# Gravador.net
KiCad netlist of a schematic drawn in EAGLE
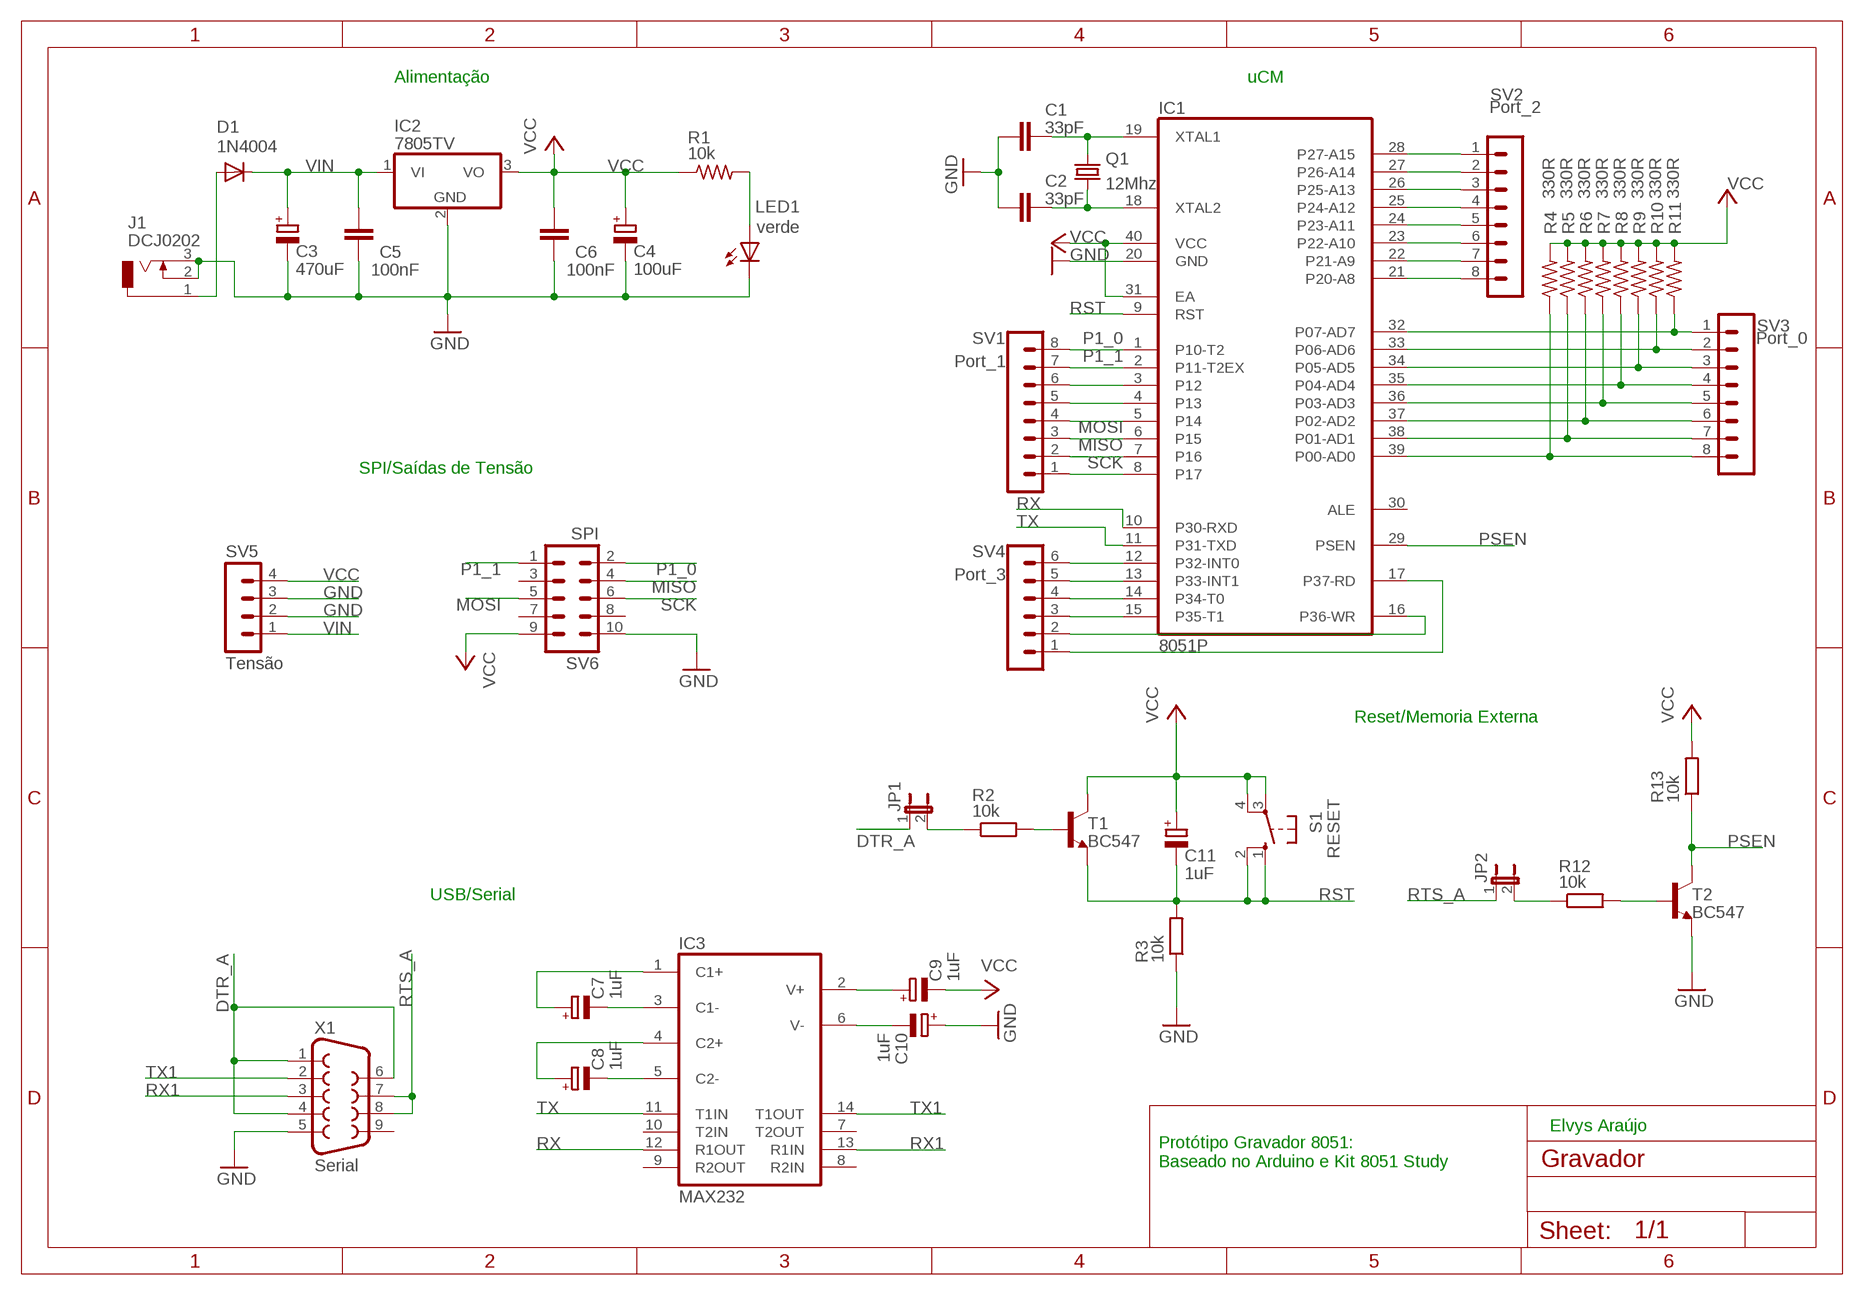
[diagram p0: schematic, sheet 1]

(export (version "E")
  (design (tool "Eeschema 10.0.6"))
  (components
    (comp (ref "C1")
      (value "33pF")
      (footprint "eagle-import:C5B3")
      (libsource (lib "eagle-import") (part "C5/3"))
    )
    (comp (ref "C2")
      (value "33pF")
      (footprint "eagle-import:C5B3")
      (libsource (lib "eagle-import") (part "C5/3"))
    )
    (comp (ref "C3")
      (value "470uF")
      (footprint "eagle-import:E3,5-8")
      (libsource (lib "eagle-import") (part "CPOL-EUE3.5-8"))
    )
    (comp (ref "C4")
      (value "100uF")
      (footprint "eagle-import:E2,5-6E")
      (libsource (lib "eagle-import") (part "CPOL-EUE2,5-6E"))
    )
    (comp (ref "C5")
      (value "100nF")
      (footprint "eagle-import:C5B3")
      (libsource (lib "eagle-import") (part "C5/3"))
    )
    (comp (ref "C6")
      (value "100nF")
      (footprint "eagle-import:C5B3")
      (libsource (lib "eagle-import") (part "C5/3"))
    )
    (comp (ref "C7")
      (value "1uF")
      (footprint "eagle-import:E2,5-6E")
      (libsource (lib "eagle-import") (part "CPOL-EUE2,5-6E"))
    )
    (comp (ref "C8")
      (value "1uF")
      (footprint "eagle-import:E2,5-6E")
      (libsource (lib "eagle-import") (part "CPOL-EUE2,5-6E"))
    )
    (comp (ref "C9")
      (value "1uF")
      (footprint "eagle-import:E2,5-6E")
      (libsource (lib "eagle-import") (part "CPOL-EUE2,5-6E"))
    )
    (comp (ref "C10")
      (value "1uF")
      (footprint "eagle-import:E2,5-6E")
      (libsource (lib "eagle-import") (part "CPOL-EUE2,5-6E"))
    )
    (comp (ref "C11")
      (value "1uF")
      (footprint "eagle-import:E2,5-6E")
      (libsource (lib "eagle-import") (part "CPOL-EUE2,5-6E"))
    )
    (comp (ref "D1")
      (value "1N4004")
      (footprint "eagle-import:DO41-10")
      (libsource (lib "eagle-import") (part "1N4004"))
    )
    (comp (ref "IC1")
      (value "8051P")
      (footprint "eagle-import:DIL40")
      (libsource (lib "eagle-import") (part "8051P"))
    )
    (comp (ref "IC2")
      (value "7805TV")
      (footprint "eagle-import:TO220V")
      (libsource (lib "eagle-import") (part "78TV05"))
    )
    (comp (ref "IC3")
      (value "MAX232")
      (footprint "eagle-import:DIL16")
      (fields (field (name "MF") "MAXIM") (field (name "MPN") "MAX232ACPE+"))
      (libsource (lib "eagle-import") (part "MAX232"))
    )
    (comp (ref "J1")
      (value "DCJ0202")
      (footprint "eagle-import:DCJ0202")
      (libsource (lib "eagle-import") (part "DCJ0202"))
    )
    (comp (ref "JP1")
      (value "JP1E")
      (footprint "eagle-import:JP1")
      (libsource (lib "eagle-import") (part "JP1E"))
    )
    (comp (ref "JP2")
      (value "JP1E")
      (footprint "eagle-import:JP1")
      (libsource (lib "eagle-import") (part "JP1E"))
    )
    (comp (ref "LED1")
      (value "verde")
      (footprint "eagle-import:LED5MM")
      (libsource (lib "eagle-import") (part "LED5MM"))
    )
    (comp (ref "Q1")
      (value "12Mhz")
      (footprint "eagle-import:HC49U-V")
      (libsource (lib "eagle-import") (part "CRYSTALHC49U-V"))
    )
    (comp (ref "R1")
      (value "10k")
      (footprint "eagle-import:0207_2V")
      (libsource (lib "eagle-import") (part "R-US_0207/2V"))
    )
    (comp (ref "R2")
      (value "10k")
      (footprint "eagle-import:0207_10@1")
      (libsource (lib "eagle-import") (part "R-EU_0207/10"))
    )
    (comp (ref "R3")
      (value "10k")
      (footprint "eagle-import:0207_10@1")
      (libsource (lib "eagle-import") (part "R-EU_0207/10"))
    )
    (comp (ref "R4")
      (value "330R")
      (footprint "eagle-import:0207_2V")
      (libsource (lib "eagle-import") (part "R-US_0207/2V"))
    )
    (comp (ref "R5")
      (value "330R")
      (footprint "eagle-import:0207_2V")
      (libsource (lib "eagle-import") (part "R-US_0207/2V"))
    )
    (comp (ref "R6")
      (value "330R")
      (footprint "eagle-import:0207_2V")
      (libsource (lib "eagle-import") (part "R-US_0207/2V"))
    )
    (comp (ref "R7")
      (value "330R")
      (footprint "eagle-import:0207_2V")
      (libsource (lib "eagle-import") (part "R-US_0207/2V"))
    )
    (comp (ref "R8")
      (value "330R")
      (footprint "eagle-import:0207_2V")
      (libsource (lib "eagle-import") (part "R-US_0207/2V"))
    )
    (comp (ref "R9")
      (value "330R")
      (footprint "eagle-import:0207_2V")
      (libsource (lib "eagle-import") (part "R-US_0207/2V"))
    )
    (comp (ref "R10")
      (value "330R")
      (footprint "eagle-import:0207_2V")
      (libsource (lib "eagle-import") (part "R-US_0207/2V"))
    )
    (comp (ref "R11")
      (value "330R")
      (footprint "eagle-import:0207_2V")
      (libsource (lib "eagle-import") (part "R-US_0207/2V"))
    )
    (comp (ref "R12")
      (value "10k")
      (footprint "eagle-import:0207_10@1")
      (libsource (lib "eagle-import") (part "R-EU_0207/10"))
    )
    (comp (ref "R13")
      (value "10k")
      (footprint "eagle-import:0207_10@1")
      (libsource (lib "eagle-import") (part "R-EU_0207/10"))
    )
    (comp (ref "S1")
      (value "RESET")
      (footprint "eagle-import:B3F-10XX")
      (fields (field (name "MPN") "B3F-1000"))
      (libsource (lib "eagle-import") (part "10-XX"))
    )
    (comp (ref "SV1")
      (value "Port_1")
      (footprint "eagle-import:MA08-1")
      (libsource (lib "eagle-import") (part "MA08-1"))
    )
    (comp (ref "SV2")
      (value "Port_2")
      (footprint "eagle-import:MA08-1")
      (libsource (lib "eagle-import") (part "MA08-1"))
    )
    (comp (ref "SV3")
      (value "Port_0")
      (footprint "eagle-import:MA08-1")
      (libsource (lib "eagle-import") (part "MA08-1"))
    )
    (comp (ref "SV4")
      (value "Port_3")
      (footprint "eagle-import:MA06-1")
      (libsource (lib "eagle-import") (part "MA06-1"))
    )
    (comp (ref "SV5")
      (value "Tensão")
      (footprint "eagle-import:MA04-1")
      (libsource (lib "eagle-import") (part "MA04-1"))
    )
    (comp (ref "SV6")
      (value "SPI")
      (footprint "eagle-import:MA05-2")
      (libsource (lib "eagle-import") (part "MA05-2"))
    )
    (comp (ref "T1")
      (value "BC547")
      (footprint "eagle-import:TO92")
      (libsource (lib "eagle-import") (part "BC547"))
    )
    (comp (ref "T2")
      (value "BC547")
      (footprint "eagle-import:TO92")
      (libsource (lib "eagle-import") (part "BC547"))
    )
    (comp (ref "X1")
      (value "Serial")
      (footprint "eagle-import:F09HP")
      (libsource (lib "eagle-import") (part "F09HP"))
    )
  )
  (nets
    (net (code "1") (name "/DTR_A") (class "Default")
      (node (ref "JP1") (pin "1") (pinfunction "1_1") (pintype "passive"))
      (node (ref "X1") (pin "1") (pinfunction "1_1") (pintype "passive"))
      (node (ref "X1") (pin "4") (pinfunction "4_4") (pintype "passive"))
      (node (ref "X1") (pin "6") (pinfunction "6_6") (pintype "passive"))
    )
    (net (code "2") (name "/MISO") (class "Default")
      (node (ref "IC1") (pin "7") (pinfunction "P16_7") (pintype "bidirectional"))
      (node (ref "SV1") (pin "2") (pinfunction "2_2") (pintype "passive"))
      (node (ref "SV6") (pin "4") (pinfunction "4_4") (pintype "passive"))
    )
    (net (code "3") (name "/MOSI") (class "Default")
      (node (ref "IC1") (pin "6") (pinfunction "P15_6") (pintype "bidirectional"))
      (node (ref "SV1") (pin "3") (pinfunction "3_3") (pintype "passive"))
      (node (ref "SV6") (pin "5") (pinfunction "5_5") (pintype "passive"))
    )
    (net (code "4") (name "/P1_0") (class "Default")
      (node (ref "IC1") (pin "1") (pinfunction "P10-T2_1") (pintype "bidirectional"))
      (node (ref "SV1") (pin "8") (pinfunction "8_8") (pintype "passive"))
      (node (ref "SV6") (pin "2") (pinfunction "2_2") (pintype "passive"))
    )
    (net (code "5") (name "/P1_1") (class "Default")
      (node (ref "IC1") (pin "2") (pinfunction "P11-T2EX_2") (pintype "bidirectional"))
      (node (ref "SV1") (pin "7") (pinfunction "7_7") (pintype "passive"))
      (node (ref "SV6") (pin "1") (pinfunction "1_1") (pintype "passive"))
    )
    (net (code "6") (name "/PSEN") (class "Default")
      (node (ref "IC1") (pin "29") (pinfunction "PSEN_29") (pintype "output"))
      (node (ref "R13") (pin "1") (pinfunction "1_1") (pintype "passive"))
      (node (ref "T2") (pin "3") (pinfunction "C_3") (pintype "passive"))
    )
    (net (code "7") (name "/RST") (class "Default")
      (node (ref "C11") (pin "-") (pinfunction "-_-") (pintype "passive"))
      (node (ref "IC1") (pin "9") (pinfunction "RST_9") (pintype "input"))
      (node (ref "R3") (pin "2") (pinfunction "2_2") (pintype "passive"))
      (node (ref "S1") (pin "1") (pinfunction "S_1") (pintype "passive"))
      (node (ref "S1") (pin "2") (pinfunction "S1_2") (pintype "passive"))
      (node (ref "T1") (pin "1") (pinfunction "E_1") (pintype "passive"))
    )
    (net (code "8") (name "/RTS_A") (class "Default")
      (node (ref "JP2") (pin "1") (pinfunction "1_1") (pintype "passive"))
      (node (ref "X1") (pin "7") (pinfunction "7_7") (pintype "passive"))
      (node (ref "X1") (pin "8") (pinfunction "8_8") (pintype "passive"))
    )
    (net (code "9") (name "/RX") (class "Default")
      (node (ref "IC1") (pin "10") (pinfunction "P30-RXD_10") (pintype "bidirectional"))
      (node (ref "IC3") (pin "12") (pinfunction "R1OUT_12") (pintype "output"))
    )
    (net (code "10") (name "/RX1") (class "Default")
      (node (ref "IC3") (pin "13") (pinfunction "R1IN_13") (pintype "input"))
      (node (ref "X1") (pin "3") (pinfunction "3_3") (pintype "passive"))
    )
    (net (code "11") (name "/SCK") (class "Default")
      (node (ref "IC1") (pin "8") (pinfunction "P17_8") (pintype "bidirectional"))
      (node (ref "SV1") (pin "1") (pinfunction "1_1") (pintype "passive"))
      (node (ref "SV6") (pin "6") (pinfunction "6_6") (pintype "passive"))
    )
    (net (code "12") (name "/TX") (class "Default")
      (node (ref "IC1") (pin "11") (pinfunction "P31-TXD_11") (pintype "bidirectional"))
      (node (ref "IC3") (pin "11") (pinfunction "T1IN_11") (pintype "input"))
    )
    (net (code "13") (name "/TX1") (class "Default")
      (node (ref "IC3") (pin "14") (pinfunction "T1OUT_14") (pintype "output"))
      (node (ref "X1") (pin "2") (pinfunction "2_2") (pintype "passive"))
    )
    (net (code "14") (name "/VIN") (class "Default")
      (node (ref "C3") (pin "+") (pinfunction "+_+") (pintype "passive"))
      (node (ref "C5") (pin "1") (pinfunction "1_1") (pintype "passive"))
      (node (ref "D1") (pin "C") (pinfunction "C_C") (pintype "passive"))
      (node (ref "IC2") (pin "1") (pinfunction "VI_1") (pintype "input"))
      (node (ref "SV5") (pin "1") (pinfunction "1_1") (pintype "passive"))
    )
    (net (code "15") (name "GND") (class "Default")
      (node (ref "C1") (pin "2") (pinfunction "2_2") (pintype "passive"))
      (node (ref "C10") (pin "+") (pinfunction "+_+") (pintype "passive"))
      (node (ref "C2") (pin "2") (pinfunction "2_2") (pintype "passive"))
      (node (ref "C3") (pin "-") (pinfunction "-_-") (pintype "passive"))
      (node (ref "C4") (pin "-") (pinfunction "-_-") (pintype "passive"))
      (node (ref "C5") (pin "2") (pinfunction "2_2") (pintype "passive"))
      (node (ref "C6") (pin "2") (pinfunction "2_2") (pintype "passive"))
      (node (ref "IC1") (pin "20") (pinfunction "GND_20") (pintype "power_in"))
      (node (ref "IC2") (pin "2") (pinfunction "GND_2") (pintype "passive"))
      (node (ref "J1") (pin "2") (pinfunction "2_2") (pintype "passive"))
      (node (ref "J1") (pin "3") (pinfunction "3_3") (pintype "passive"))
      (node (ref "LED1") (pin "K") (pinfunction "C_K") (pintype "passive"))
      (node (ref "R3") (pin "1") (pinfunction "1_1") (pintype "passive"))
      (node (ref "SV5") (pin "2") (pinfunction "2_2") (pintype "passive"))
      (node (ref "SV5") (pin "3") (pinfunction "3_3") (pintype "passive"))
      (node (ref "SV6") (pin "10") (pinfunction "10_10") (pintype "passive"))
      (node (ref "T2") (pin "1") (pinfunction "E_1") (pintype "passive"))
      (node (ref "X1") (pin "5") (pinfunction "5_5") (pintype "passive"))
    )
    (net (code "16") (name "Net-(D1-PadA)") (class "Default")
      (node (ref "D1") (pin "A") (pinfunction "A_A") (pintype "passive"))
      (node (ref "J1") (pin "1") (pinfunction "1_1") (pintype "passive"))
    )
    (net (code "17") (name "Net-(IC1-P00-AD0)") (class "Default")
      (node (ref "IC1") (pin "39") (pinfunction "P00-AD0_39") (pintype "bidirectional"))
      (node (ref "R4") (pin "1") (pinfunction "1_1") (pintype "passive"))
      (node (ref "SV3") (pin "8") (pinfunction "8_8") (pintype "passive"))
    )
    (net (code "18") (name "Net-(IC1-P01-AD1)") (class "Default")
      (node (ref "IC1") (pin "38") (pinfunction "P01-AD1_38") (pintype "bidirectional"))
      (node (ref "R5") (pin "1") (pinfunction "1_1") (pintype "passive"))
      (node (ref "SV3") (pin "7") (pinfunction "7_7") (pintype "passive"))
    )
    (net (code "19") (name "Net-(IC1-P02-AD2)") (class "Default")
      (node (ref "IC1") (pin "37") (pinfunction "P02-AD2_37") (pintype "bidirectional"))
      (node (ref "R6") (pin "1") (pinfunction "1_1") (pintype "passive"))
      (node (ref "SV3") (pin "6") (pinfunction "6_6") (pintype "passive"))
    )
    (net (code "20") (name "Net-(IC1-P03-AD3)") (class "Default")
      (node (ref "IC1") (pin "36") (pinfunction "P03-AD3_36") (pintype "bidirectional"))
      (node (ref "R7") (pin "1") (pinfunction "1_1") (pintype "passive"))
      (node (ref "SV3") (pin "5") (pinfunction "5_5") (pintype "passive"))
    )
    (net (code "21") (name "Net-(IC1-P04-AD4)") (class "Default")
      (node (ref "IC1") (pin "35") (pinfunction "P04-AD4_35") (pintype "bidirectional"))
      (node (ref "R8") (pin "1") (pinfunction "1_1") (pintype "passive"))
      (node (ref "SV3") (pin "4") (pinfunction "4_4") (pintype "passive"))
    )
    (net (code "22") (name "Net-(IC1-P05-AD5)") (class "Default")
      (node (ref "IC1") (pin "34") (pinfunction "P05-AD5_34") (pintype "bidirectional"))
      (node (ref "R9") (pin "1") (pinfunction "1_1") (pintype "passive"))
      (node (ref "SV3") (pin "3") (pinfunction "3_3") (pintype "passive"))
    )
    (net (code "23") (name "Net-(IC1-P06-AD6)") (class "Default")
      (node (ref "IC1") (pin "33") (pinfunction "P06-AD6_33") (pintype "bidirectional"))
      (node (ref "R10") (pin "1") (pinfunction "1_1") (pintype "passive"))
      (node (ref "SV3") (pin "2") (pinfunction "2_2") (pintype "passive"))
    )
    (net (code "24") (name "Net-(IC1-P07-AD7)") (class "Default")
      (node (ref "IC1") (pin "32") (pinfunction "P07-AD7_32") (pintype "bidirectional"))
      (node (ref "R11") (pin "1") (pinfunction "1_1") (pintype "passive"))
      (node (ref "SV3") (pin "1") (pinfunction "1_1") (pintype "passive"))
    )
    (net (code "25") (name "Net-(IC1-P12)") (class "Default")
      (node (ref "IC1") (pin "3") (pinfunction "P12_3") (pintype "bidirectional"))
      (node (ref "SV1") (pin "6") (pinfunction "6_6") (pintype "passive"))
    )
    (net (code "26") (name "Net-(IC1-P13)") (class "Default")
      (node (ref "IC1") (pin "4") (pinfunction "P13_4") (pintype "bidirectional"))
      (node (ref "SV1") (pin "5") (pinfunction "5_5") (pintype "passive"))
    )
    (net (code "27") (name "Net-(IC1-P14)") (class "Default")
      (node (ref "IC1") (pin "5") (pinfunction "P14_5") (pintype "bidirectional"))
      (node (ref "SV1") (pin "4") (pinfunction "4_4") (pintype "passive"))
    )
    (net (code "28") (name "Net-(IC1-P20-A8)") (class "Default")
      (node (ref "IC1") (pin "21") (pinfunction "P20-A8_21") (pintype "bidirectional"))
      (node (ref "SV2") (pin "8") (pinfunction "8_8") (pintype "passive"))
    )
    (net (code "29") (name "Net-(IC1-P21-A9)") (class "Default")
      (node (ref "IC1") (pin "22") (pinfunction "P21-A9_22") (pintype "bidirectional"))
      (node (ref "SV2") (pin "7") (pinfunction "7_7") (pintype "passive"))
    )
    (net (code "30") (name "Net-(IC1-P22-A10)") (class "Default")
      (node (ref "IC1") (pin "23") (pinfunction "P22-A10_23") (pintype "bidirectional"))
      (node (ref "SV2") (pin "6") (pinfunction "6_6") (pintype "passive"))
    )
    (net (code "31") (name "Net-(IC1-P23-A11)") (class "Default")
      (node (ref "IC1") (pin "24") (pinfunction "P23-A11_24") (pintype "bidirectional"))
      (node (ref "SV2") (pin "5") (pinfunction "5_5") (pintype "passive"))
    )
    (net (code "32") (name "Net-(IC1-P24-A12)") (class "Default")
      (node (ref "IC1") (pin "25") (pinfunction "P24-A12_25") (pintype "bidirectional"))
      (node (ref "SV2") (pin "4") (pinfunction "4_4") (pintype "passive"))
    )
    (net (code "33") (name "Net-(IC1-P25-A13)") (class "Default")
      (node (ref "IC1") (pin "26") (pinfunction "P25-A13_26") (pintype "bidirectional"))
      (node (ref "SV2") (pin "3") (pinfunction "3_3") (pintype "passive"))
    )
    (net (code "34") (name "Net-(IC1-P26-A14)") (class "Default")
      (node (ref "IC1") (pin "27") (pinfunction "P26-A14_27") (pintype "bidirectional"))
      (node (ref "SV2") (pin "2") (pinfunction "2_2") (pintype "passive"))
    )
    (net (code "35") (name "Net-(IC1-P27-A15)") (class "Default")
      (node (ref "IC1") (pin "28") (pinfunction "P27-A15_28") (pintype "bidirectional"))
      (node (ref "SV2") (pin "1") (pinfunction "1_1") (pintype "passive"))
    )
    (net (code "36") (name "Net-(IC1-P32-INT0)") (class "Default")
      (node (ref "IC1") (pin "12") (pinfunction "P32-INT0_12") (pintype "bidirectional"))
      (node (ref "SV4") (pin "6") (pinfunction "6_6") (pintype "passive"))
    )
    (net (code "37") (name "Net-(IC1-P33-INT1)") (class "Default")
      (node (ref "IC1") (pin "13") (pinfunction "P33-INT1_13") (pintype "bidirectional"))
      (node (ref "SV4") (pin "5") (pinfunction "5_5") (pintype "passive"))
    )
    (net (code "38") (name "Net-(IC1-P34-T0)") (class "Default")
      (node (ref "IC1") (pin "14") (pinfunction "P34-T0_14") (pintype "bidirectional"))
      (node (ref "SV4") (pin "4") (pinfunction "4_4") (pintype "passive"))
    )
    (net (code "39") (name "Net-(IC1-P35-T1)") (class "Default")
      (node (ref "IC1") (pin "15") (pinfunction "P35-T1_15") (pintype "bidirectional"))
      (node (ref "SV4") (pin "3") (pinfunction "3_3") (pintype "passive"))
    )
    (net (code "40") (name "Net-(IC1-P36-WR)") (class "Default")
      (node (ref "IC1") (pin "16") (pinfunction "P36-WR_16") (pintype "bidirectional"))
      (node (ref "SV4") (pin "2") (pinfunction "2_2") (pintype "passive"))
    )
    (net (code "41") (name "Net-(IC1-P37-RD)") (class "Default")
      (node (ref "IC1") (pin "17") (pinfunction "P37-RD_17") (pintype "bidirectional"))
      (node (ref "SV4") (pin "1") (pinfunction "1_1") (pintype "passive"))
    )
    (net (code "42") (name "Net-(IC1-XTAL1)") (class "Default")
      (node (ref "C1") (pin "1") (pinfunction "1_1") (pintype "passive"))
      (node (ref "IC1") (pin "19") (pinfunction "XTAL1_19") (pintype "input"))
      (node (ref "Q1") (pin "1") (pinfunction "1_1") (pintype "passive"))
    )
    (net (code "43") (name "Net-(IC1-XTAL2)") (class "Default")
      (node (ref "C2") (pin "1") (pinfunction "1_1") (pintype "passive"))
      (node (ref "IC1") (pin "18") (pinfunction "XTAL2_18") (pintype "input"))
      (node (ref "Q1") (pin "2") (pinfunction "2_2") (pintype "passive"))
    )
    (net (code "44") (name "Net-(IC3A-C1+)") (class "Default")
      (node (ref "C7") (pin "+") (pinfunction "+_+") (pintype "passive"))
      (node (ref "IC3") (pin "1") (pinfunction "C1+_1") (pintype "bidirectional"))
    )
    (net (code "45") (name "Net-(IC3A-C1-)") (class "Default")
      (node (ref "C7") (pin "-") (pinfunction "-_-") (pintype "passive"))
      (node (ref "IC3") (pin "3") (pinfunction "C1-_3") (pintype "bidirectional"))
    )
    (net (code "46") (name "Net-(IC3A-C2+)") (class "Default")
      (node (ref "C8") (pin "+") (pinfunction "+_+") (pintype "passive"))
      (node (ref "IC3") (pin "4") (pinfunction "C2+_4") (pintype "bidirectional"))
    )
    (net (code "47") (name "Net-(IC3A-C2-)") (class "Default")
      (node (ref "C8") (pin "-") (pinfunction "-_-") (pintype "passive"))
      (node (ref "IC3") (pin "5") (pinfunction "C2-_5") (pintype "bidirectional"))
    )
    (net (code "48") (name "Net-(IC3A-V+)") (class "Default")
      (node (ref "C9") (pin "+") (pinfunction "+_+") (pintype "passive"))
      (node (ref "IC3") (pin "2") (pinfunction "V+_2") (pintype "bidirectional"))
    )
    (net (code "49") (name "Net-(IC3A-V-)") (class "Default")
      (node (ref "C10") (pin "-") (pinfunction "-_-") (pintype "passive"))
      (node (ref "IC3") (pin "6") (pinfunction "V-_6") (pintype "bidirectional"))
    )
    (net (code "50") (name "Net-(JP1-Pad2)") (class "Default")
      (node (ref "JP1") (pin "2") (pinfunction "2_2") (pintype "passive"))
      (node (ref "R2") (pin "1") (pinfunction "1_1") (pintype "passive"))
    )
    (net (code "51") (name "Net-(JP2-Pad2)") (class "Default")
      (node (ref "JP2") (pin "2") (pinfunction "2_2") (pintype "passive"))
      (node (ref "R12") (pin "1") (pinfunction "1_1") (pintype "passive"))
    )
    (net (code "52") (name "Net-(LED1-PadA)") (class "Default")
      (node (ref "LED1") (pin "A") (pinfunction "A_A") (pintype "passive"))
      (node (ref "R1") (pin "2") (pinfunction "2_2") (pintype "passive"))
    )
    (net (code "53") (name "Net-(T1-B)") (class "Default")
      (node (ref "R2") (pin "2") (pinfunction "2_2") (pintype "passive"))
      (node (ref "T1") (pin "2") (pinfunction "B_2") (pintype "passive"))
    )
    (net (code "54") (name "Net-(T2-B)") (class "Default")
      (node (ref "R12") (pin "2") (pinfunction "2_2") (pintype "passive"))
      (node (ref "T2") (pin "2") (pinfunction "B_2") (pintype "passive"))
    )
    (net (code "55") (name "VCC") (class "Default")
      (node (ref "C11") (pin "+") (pinfunction "+_+") (pintype "passive"))
      (node (ref "C4") (pin "+") (pinfunction "+_+") (pintype "passive"))
      (node (ref "C6") (pin "1") (pinfunction "1_1") (pintype "passive"))
      (node (ref "C9") (pin "-") (pinfunction "-_-") (pintype "passive"))
      (node (ref "IC1") (pin "31") (pinfunction "EA_31") (pintype "input"))
      (node (ref "IC1") (pin "40") (pinfunction "VCC_40") (pintype "power_in"))
      (node (ref "IC2") (pin "3") (pinfunction "VO_3") (pintype "passive"))
      (node (ref "R1") (pin "1") (pinfunction "1_1") (pintype "passive"))
      (node (ref "R10") (pin "2") (pinfunction "2_2") (pintype "passive"))
      (node (ref "R11") (pin "2") (pinfunction "2_2") (pintype "passive"))
      (node (ref "R13") (pin "2") (pinfunction "2_2") (pintype "passive"))
      (node (ref "R4") (pin "2") (pinfunction "2_2") (pintype "passive"))
      (node (ref "R5") (pin "2") (pinfunction "2_2") (pintype "passive"))
      (node (ref "R6") (pin "2") (pinfunction "2_2") (pintype "passive"))
      (node (ref "R7") (pin "2") (pinfunction "2_2") (pintype "passive"))
      (node (ref "R8") (pin "2") (pinfunction "2_2") (pintype "passive"))
      (node (ref "R9") (pin "2") (pinfunction "2_2") (pintype "passive"))
      (node (ref "S1") (pin "3") (pinfunction "P_3") (pintype "passive"))
      (node (ref "S1") (pin "4") (pinfunction "P1_4") (pintype "passive"))
      (node (ref "SV5") (pin "4") (pinfunction "4_4") (pintype "passive"))
      (node (ref "SV6") (pin "9") (pinfunction "9_9") (pintype "passive"))
      (node (ref "T1") (pin "3") (pinfunction "C_3") (pintype "passive"))
    )
    (net (code "56") (name "unconnected-(IC1-ALE-Pad30)") (class "Default")
      (node (ref "IC1") (pin "30") (pinfunction "ALE_30") (pintype "output"))
    )
    (net (code "57") (name "unconnected-(IC3A-R2IN-Pad8)") (class "Default")
      (node (ref "IC3") (pin "8") (pinfunction "R2IN_8") (pintype "input"))
    )
    (net (code "58") (name "unconnected-(IC3A-R2OUT-Pad9)") (class "Default")
      (node (ref "IC3") (pin "9") (pinfunction "R2OUT_9") (pintype "output"))
    )
    (net (code "59") (name "unconnected-(IC3A-T2IN-Pad10)") (class "Default")
      (node (ref "IC3") (pin "10") (pinfunction "T2IN_10") (pintype "input"))
    )
    (net (code "60") (name "unconnected-(IC3A-T2OUT-Pad7)") (class "Default")
      (node (ref "IC3") (pin "7") (pinfunction "T2OUT_7") (pintype "output"))
    )
    (net (code "61") (name "unconnected-(SV6-Pad3)") (class "Default")
      (node (ref "SV6") (pin "3") (pinfunction "3_3") (pintype "passive"))
    )
    (net (code "62") (name "unconnected-(SV6-Pad7)") (class "Default")
      (node (ref "SV6") (pin "7") (pinfunction "7_7") (pintype "passive"))
    )
    (net (code "63") (name "unconnected-(SV6-Pad8)") (class "Default")
      (node (ref "SV6") (pin "8") (pinfunction "8_8") (pintype "passive"))
    )
    (net (code "64") (name "unconnected-(X1-Pad9)") (class "Default")
      (node (ref "X1") (pin "9") (pinfunction "9_9") (pintype "passive"))
    )
  )
)
